# Ultra_Water.net
KiCad netlist of a schematic drawn in EAGLE
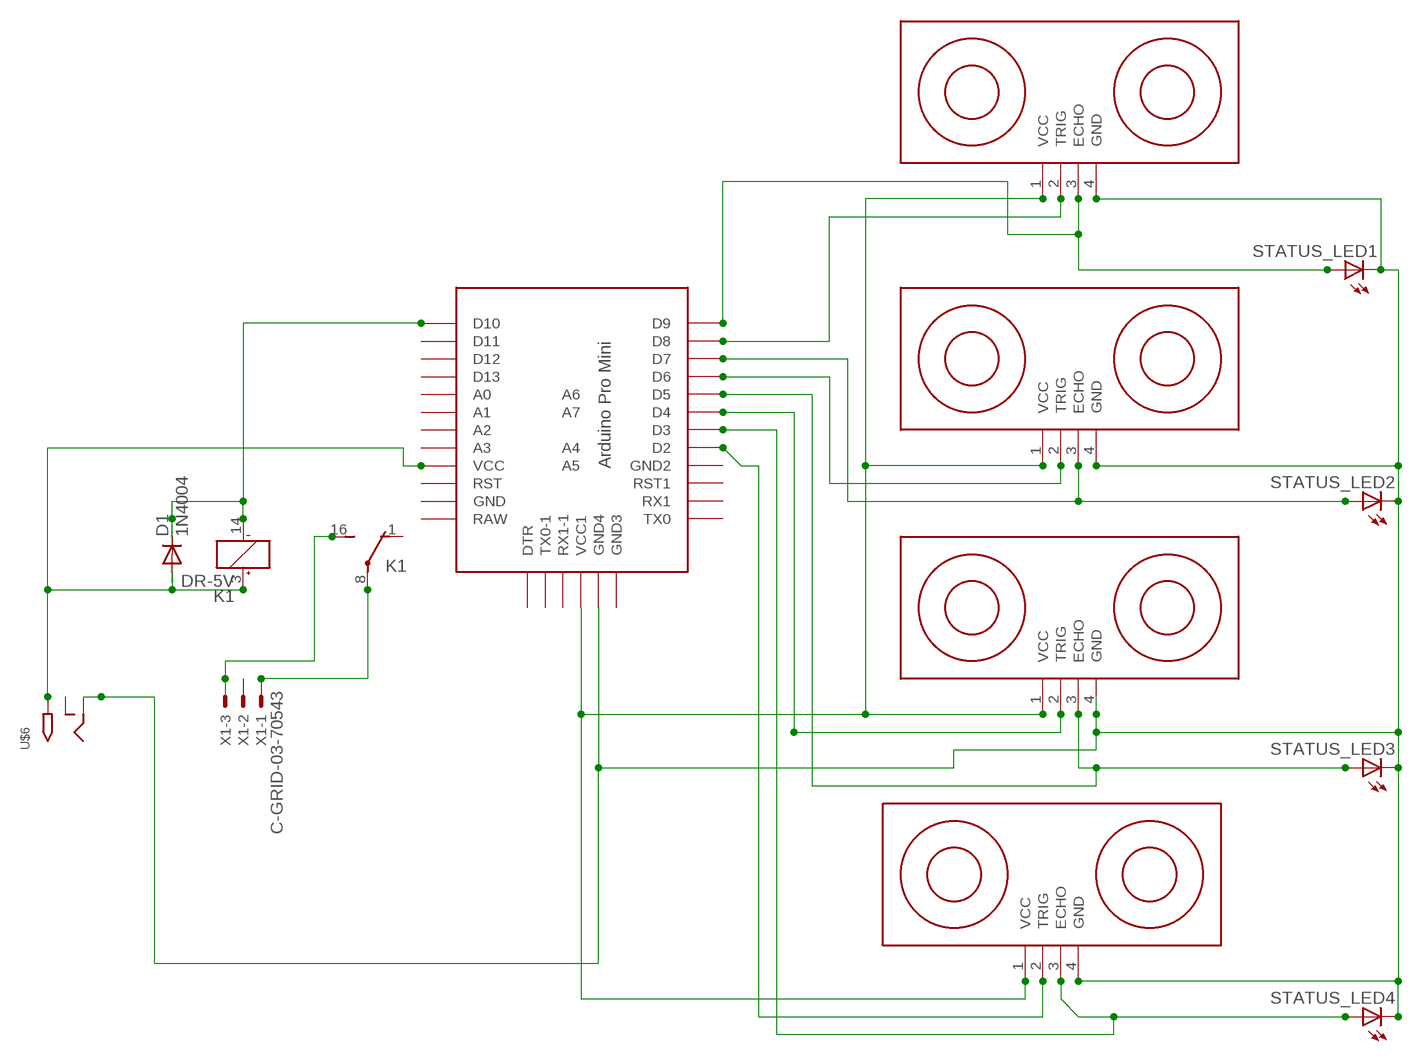
[diagram p0: schematic, sheet 1]

(export (version "E")
  (design (tool "Eeschema 10.0.6"))
  (components
    (comp (ref "D1")
      (value "1N4004")
      (footprint "eagle-import:DO41-10")
      (libsource (lib "eagle-import") (part "1N4004"))
    )
    (comp (ref "K1")
      (value "DR-5V")
      (footprint "eagle-import:DR-1")
      (libsource (lib "eagle-import") (part "DR-V5"))
    )
    (comp (ref "STATUS_LED1")
      (value "LED5MM")
      (footprint "eagle-import:LED5MM")
      (libsource (lib "eagle-import") (part "LED5MM"))
    )
    (comp (ref "STATUS_LED2")
      (value "LED5MM")
      (footprint "eagle-import:LED5MM")
      (libsource (lib "eagle-import") (part "LED5MM"))
    )
    (comp (ref "STATUS_LED3")
      (value "LED5MM")
      (footprint "eagle-import:LED5MM")
      (libsource (lib "eagle-import") (part "LED5MM"))
    )
    (comp (ref "STATUS_LED4")
      (value "LED5MM")
      (footprint "eagle-import:LED5MM")
      (libsource (lib "eagle-import") (part "LED5MM"))
    )
    (comp (ref "U$1")
      (value "PRO-MINI-2")
      (footprint "eagle-import:PRO-MINI-2")
      (libsource (lib "eagle-import") (part "PRO-MINI-2"))
    )
    (comp (ref "U$2")
      (value "ULTRASONIC-HC-SR04")
      (footprint "eagle-import:ULTRASONIC-HC-SR04")
      (libsource (lib "eagle-import") (part "ULTRASONIC-HC-SR04"))
    )
    (comp (ref "U$3")
      (value "ULTRASONIC-HC-SR04")
      (footprint "eagle-import:ULTRASONIC-HC-SR04")
      (libsource (lib "eagle-import") (part "ULTRASONIC-HC-SR04"))
    )
    (comp (ref "U$4")
      (value "ULTRASONIC-HC-SR04")
      (footprint "eagle-import:ULTRASONIC-HC-SR04")
      (libsource (lib "eagle-import") (part "ULTRASONIC-HC-SR04"))
    )
    (comp (ref "U$5")
      (value "ULTRASONIC-HC-SR04")
      (footprint "eagle-import:ULTRASONIC-HC-SR04")
      (libsource (lib "eagle-import") (part "ULTRASONIC-HC-SR04"))
    )
    (comp (ref "U$6")
      (value "2.1MMJACKTHM")
      (footprint "eagle-import:PJ-102A")
      (libsource (lib "eagle-import") (part "2.1MMJACKTHM"))
    )
    (comp (ref "X1")
      (value "C-GRID-03-70543")
      (footprint "eagle-import:70543-03")
      (libsource (lib "eagle-import") (part "C-GRID-03-70543"))
    )
  )
  (nets
    (net (code "1") (name "Net-(K1A-+)") (class "Default")
      (node (ref "D1") (pin "A") (pinfunction "A_A") (pintype "passive"))
      (node (ref "K1") (pin "3") (pinfunction "+_3") (pintype "passive"))
      (node (ref "U$1") (pin "VCC") (pinfunction "VCC_VCC") (pintype "bidirectional"))
      (node (ref "U$6") (pin "TIP") (pinfunction "TIP_TIP") (pintype "bidirectional"))
    )
    (net (code "2") (name "Net-(K1A--)") (class "Default")
      (node (ref "D1") (pin "C") (pinfunction "C_C") (pintype "passive"))
      (node (ref "K1") (pin "14") (pinfunction "-_14") (pintype "passive"))
      (node (ref "U$1") (pin "D10") (pinfunction "D10_D10") (pintype "bidirectional"))
    )
    (net (code "3") (name "Net-(K1B-P)") (class "Default")
      (node (ref "K1") (pin "8") (pinfunction "P_8") (pintype "passive"))
      (node (ref "X1") (pin "1") (pinfunction "S_1") (pintype "passive"))
    )
    (net (code "4") (name "Net-(K1B-S)") (class "Default")
      (node (ref "K1") (pin "16") (pinfunction "S_16") (pintype "passive"))
      (node (ref "X1") (pin "3") (pinfunction "S_3") (pintype "passive"))
    )
    (net (code "5") (name "Net-(STATUS_LED1-C)") (class "Default")
      (node (ref "STATUS_LED1") (pin "K") (pinfunction "C_K") (pintype "passive"))
      (node (ref "STATUS_LED2") (pin "K") (pinfunction "C_K") (pintype "passive"))
      (node (ref "STATUS_LED3") (pin "K") (pinfunction "C_K") (pintype "passive"))
      (node (ref "STATUS_LED4") (pin "K") (pinfunction "C_K") (pintype "passive"))
      (node (ref "U$1") (pin "GND3") (pinfunction "GND4_GND3") (pintype "bidirectional"))
      (node (ref "U$2") (pin "4") (pinfunction "GND_4") (pintype "power_in"))
      (node (ref "U$3") (pin "4") (pinfunction "GND_4") (pintype "power_in"))
      (node (ref "U$4") (pin "4") (pinfunction "GND_4") (pintype "power_in"))
      (node (ref "U$5") (pin "4") (pinfunction "GND_4") (pintype "power_in"))
      (node (ref "U$6") (pin "RING") (pinfunction "RING_RING") (pintype "bidirectional"))
    )
    (net (code "6") (name "Net-(U$2-ECHO)") (class "Default")
      (node (ref "STATUS_LED1") (pin "A") (pinfunction "A_A") (pintype "passive"))
      (node (ref "U$1") (pin "D9") (pinfunction "D9_D9") (pintype "bidirectional"))
      (node (ref "U$2") (pin "3") (pinfunction "ECHO_3") (pintype "output"))
    )
    (net (code "7") (name "Net-(U$2-TRIG)") (class "Default")
      (node (ref "U$1") (pin "D8") (pinfunction "D8_D8") (pintype "bidirectional"))
      (node (ref "U$2") (pin "2") (pinfunction "TRIG_2") (pintype "input"))
    )
    (net (code "8") (name "Net-(U$2-VCC)") (class "Default")
      (node (ref "U$1") (pin "VCC1") (pinfunction "VCC1_VCC1") (pintype "bidirectional"))
      (node (ref "U$2") (pin "1") (pinfunction "VCC_1") (pintype "power_in"))
      (node (ref "U$3") (pin "1") (pinfunction "VCC_1") (pintype "power_in"))
      (node (ref "U$4") (pin "1") (pinfunction "VCC_1") (pintype "power_in"))
      (node (ref "U$5") (pin "1") (pinfunction "VCC_1") (pintype "power_in"))
    )
    (net (code "9") (name "Net-(U$3-ECHO)") (class "Default")
      (node (ref "STATUS_LED2") (pin "A") (pinfunction "A_A") (pintype "passive"))
      (node (ref "U$1") (pin "D7") (pinfunction "D7_D7") (pintype "bidirectional"))
      (node (ref "U$3") (pin "3") (pinfunction "ECHO_3") (pintype "output"))
    )
    (net (code "10") (name "Net-(U$3-TRIG)") (class "Default")
      (node (ref "U$1") (pin "D6") (pinfunction "D6_D6") (pintype "bidirectional"))
      (node (ref "U$3") (pin "2") (pinfunction "TRIG_2") (pintype "input"))
    )
    (net (code "11") (name "Net-(U$4-ECHO)") (class "Default")
      (node (ref "STATUS_LED3") (pin "A") (pinfunction "A_A") (pintype "passive"))
      (node (ref "U$1") (pin "D5") (pinfunction "D5_D5") (pintype "bidirectional"))
      (node (ref "U$4") (pin "3") (pinfunction "ECHO_3") (pintype "output"))
    )
    (net (code "12") (name "Net-(U$4-TRIG)") (class "Default")
      (node (ref "U$1") (pin "D4") (pinfunction "D4_D4") (pintype "bidirectional"))
      (node (ref "U$4") (pin "2") (pinfunction "TRIG_2") (pintype "input"))
    )
    (net (code "13") (name "Net-(U$5-ECHO)") (class "Default")
      (node (ref "STATUS_LED4") (pin "A") (pinfunction "A_A") (pintype "passive"))
      (node (ref "U$1") (pin "D3") (pinfunction "D3_D3") (pintype "bidirectional"))
      (node (ref "U$5") (pin "3") (pinfunction "ECHO_3") (pintype "output"))
    )
    (net (code "14") (name "Net-(U$5-TRIG)") (class "Default")
      (node (ref "U$1") (pin "D2") (pinfunction "D2_D2") (pintype "bidirectional"))
      (node (ref "U$5") (pin "2") (pinfunction "TRIG_2") (pintype "input"))
    )
    (net (code "15") (name "unconnected-(K1B-O-Pad1)") (class "Default")
      (node (ref "K1") (pin "1") (pinfunction "O_1") (pintype "passive"))
    )
    (net (code "16") (name "unconnected-(U$1-GND2-PadGND1)") (class "Default")
      (node (ref "U$1") (pin "GND1") (pinfunction "GND2_GND1") (pintype "bidirectional"))
    )
    (net (code "17") (name "unconnected-(U$1-GND3-PadGND2)") (class "Default")
      (node (ref "U$1") (pin "GND2") (pinfunction "GND3_GND2") (pintype "bidirectional"))
    )
    (net (code "18") (name "unconnected-(U$1-PadA0)") (class "Default")
      (node (ref "U$1") (pin "A0") (pinfunction "A0_A0") (pintype "bidirectional"))
    )
    (net (code "19") (name "unconnected-(U$1-PadA1)") (class "Default")
      (node (ref "U$1") (pin "A1") (pinfunction "A1_A1") (pintype "bidirectional"))
    )
    (net (code "20") (name "unconnected-(U$1-PadA2)") (class "Default")
      (node (ref "U$1") (pin "A2") (pinfunction "A2_A2") (pintype "bidirectional"))
    )
    (net (code "21") (name "unconnected-(U$1-PadA3)") (class "Default")
      (node (ref "U$1") (pin "A3") (pinfunction "A3_A3") (pintype "bidirectional"))
    )
    (net (code "22") (name "unconnected-(U$1-PadA4)") (class "Default")
      (node (ref "U$1") (pin "A4") (pinfunction "A4_A4") (pintype "bidirectional"))
    )
    (net (code "23") (name "unconnected-(U$1-PadA5)") (class "Default")
      (node (ref "U$1") (pin "A5") (pinfunction "A5_A5") (pintype "bidirectional"))
    )
    (net (code "24") (name "unconnected-(U$1-PadA6)") (class "Default")
      (node (ref "U$1") (pin "A6") (pinfunction "A6_A6") (pintype "bidirectional"))
    )
    (net (code "25") (name "unconnected-(U$1-PadA7)") (class "Default")
      (node (ref "U$1") (pin "A7") (pinfunction "A7_A7") (pintype "bidirectional"))
    )
    (net (code "26") (name "unconnected-(U$1-PadD11)") (class "Default")
      (node (ref "U$1") (pin "D11") (pinfunction "D11_D11") (pintype "bidirectional"))
    )
    (net (code "27") (name "unconnected-(U$1-PadD12)") (class "Default")
      (node (ref "U$1") (pin "D12") (pinfunction "D12_D12") (pintype "bidirectional"))
    )
    (net (code "28") (name "unconnected-(U$1-PadD13)") (class "Default")
      (node (ref "U$1") (pin "D13") (pinfunction "D13_D13") (pintype "bidirectional"))
    )
    (net (code "29") (name "unconnected-(U$1-PadDTR)") (class "Default")
      (node (ref "U$1") (pin "DTR") (pinfunction "DTR_DTR") (pintype "bidirectional"))
    )
    (net (code "30") (name "unconnected-(U$1-PadGND)") (class "Default")
      (node (ref "U$1") (pin "GND") (pinfunction "GND_GND") (pintype "bidirectional"))
    )
    (net (code "31") (name "unconnected-(U$1-PadRAW)") (class "Default")
      (node (ref "U$1") (pin "RAW") (pinfunction "RAW_RAW") (pintype "bidirectional"))
    )
    (net (code "32") (name "unconnected-(U$1-PadRST)") (class "Default")
      (node (ref "U$1") (pin "RST") (pinfunction "RST_RST") (pintype "bidirectional"))
    )
    (net (code "33") (name "unconnected-(U$1-PadRST1)") (class "Default")
      (node (ref "U$1") (pin "RST1") (pinfunction "RST1_RST1") (pintype "bidirectional"))
    )
    (net (code "34") (name "unconnected-(U$1-PadRX1)") (class "Default")
      (node (ref "U$1") (pin "RX1") (pinfunction "RX1_RX1") (pintype "bidirectional"))
    )
    (net (code "35") (name "unconnected-(U$1-PadRX1-1)") (class "Default")
      (node (ref "U$1") (pin "RX1-1") (pinfunction "RX1-1_RX1-1") (pintype "bidirectional"))
    )
    (net (code "36") (name "unconnected-(U$1-PadTX0)") (class "Default")
      (node (ref "U$1") (pin "TX0") (pinfunction "TX0_TX0") (pintype "bidirectional"))
    )
    (net (code "37") (name "unconnected-(U$1-PadTX0-1)") (class "Default")
      (node (ref "U$1") (pin "TX0-1") (pinfunction "TX0-1_TX0-1") (pintype "bidirectional"))
    )
    (net (code "38") (name "unconnected-(U$6-PadRING_SW)") (class "Default")
      (node (ref "U$6") (pin "RING_SW") (pinfunction "RING_SW_RING_SW") (pintype "bidirectional"))
    )
    (net (code "39") (name "unconnected-(X1B-S-Pad2)") (class "Default")
      (node (ref "X1") (pin "2") (pinfunction "S_2") (pintype "passive"))
    )
  )
)
